# attinier84-motherboard-mk-4_0.net
KiCad netlist of a schematic drawn in EAGLE
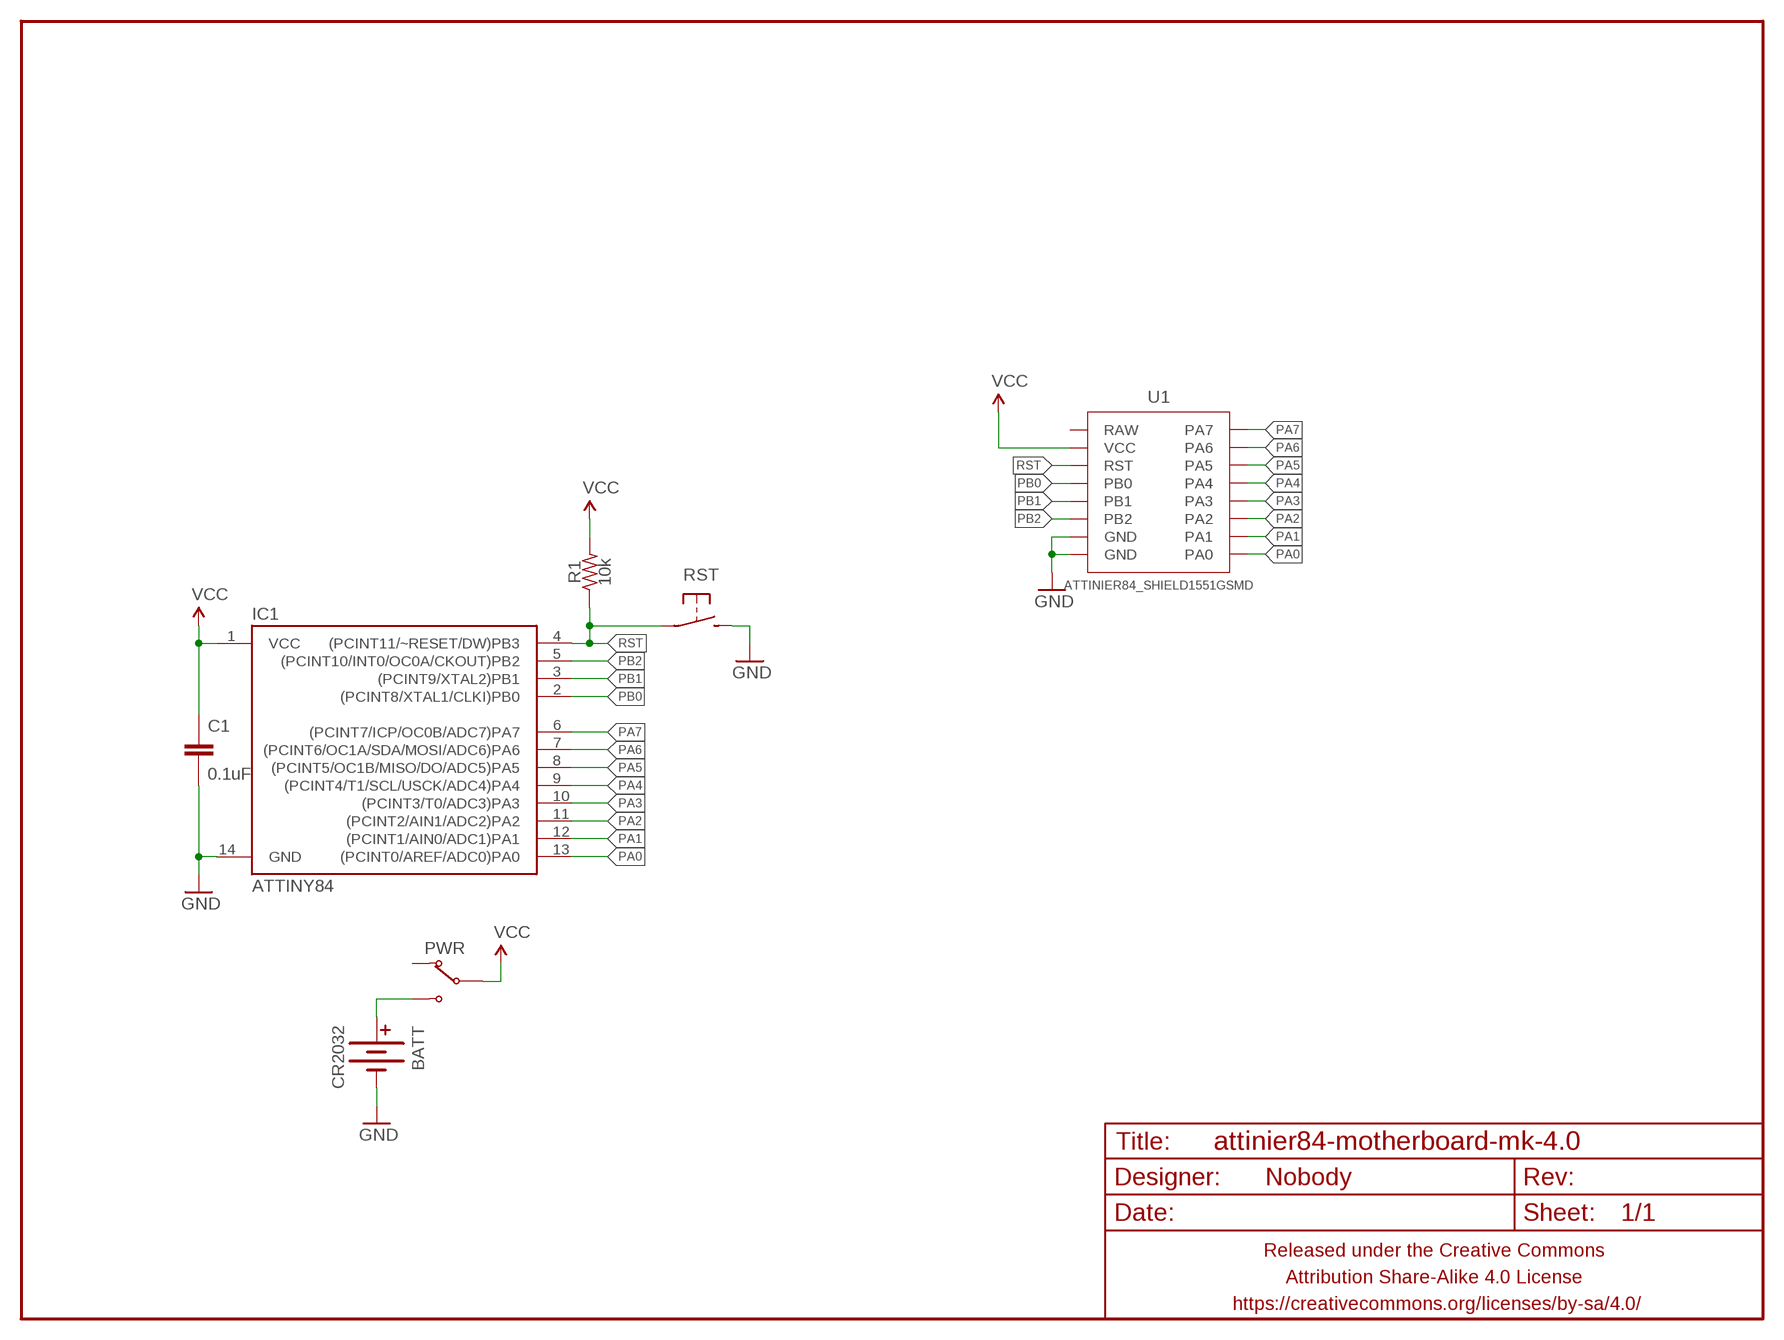
[diagram p0: schematic, sheet 1]

(export (version "E")
  (design (tool "Eeschema 10.0.6"))
  (components
    (comp (ref "BATT")
      (value "CR2032")
      (footprint "eagle-import:BATTCON_20MM_MINE_STAHPIT")
      (libsource (lib "eagle-import") (part "BATTERY20MM_SMD_TIGHT"))
    )
    (comp (ref "C1")
      (value "0.1uF")
      (footprint "eagle-import:C0805")
      (libsource (lib "eagle-import") (part "CAPACITOR-CERAMICC0805"))
    )
    (comp (ref "FRAME1")
      (value "FRAME-LETTERNO_PACKAGE")
      (footprint "eagle-import:DUMMY")
      (fields (field (name "DESIGNER") "Nobody"))
      (libsource (lib "eagle-import") (part "FRAME-LETTERNO_PACKAGE"))
    )
    (comp (ref "IC1")
      (value "ATTINY84")
      (footprint "eagle-import:SO14")
      (libsource (lib "eagle-import") (part "ATTINY84"))
    )
    (comp (ref "PWR")
      (value "SWITCH-SPDTPTH-RA-2.54MM")
      (footprint "eagle-import:SPDT-RA-2.54MM")
      (libsource (lib "eagle-import") (part "SWITCH-SPDTPTH-RA-2.54MM"))
    )
    (comp (ref "R1")
      (value "10k")
      (footprint "eagle-import:R0805")
      (libsource (lib "eagle-import") (part "RESISTORR0805"))
    )
    (comp (ref "RST")
      (value "SPST-NO-TACTCK-PTS840-GK")
      (footprint "eagle-import:TACTILE-SMD-CK-PTS840-GK")
      (libsource (lib "eagle-import") (part "SPST-NO-TACTCK-PTS840-GK"))
    )
    (comp (ref "U1")
      (value "ATTINIER84_SHIELD1551GSMD")
      (footprint "eagle-import:ATTINIER84_SHIELD2_SMD")
      (libsource (lib "eagle-import") (part "ATTINIER84_SHIELD1551GSMD"))
    )
  )
  (nets
    (net (code "1") (name "GND") (class "Default")
      (node (ref "BATT") (pin "BOTTOM") (pinfunction "-_BOTTOM") (pintype "power_in"))
      (node (ref "C1") (pin "2") (pinfunction "2_2") (pintype "passive"))
      (node (ref "IC1") (pin "14") (pinfunction "GND_14") (pintype "bidirectional"))
      (node (ref "RST") (pin "3") (pinfunction "2_3") (pintype "passive"))
      (node (ref "RST") (pin "4") (pinfunction "2_4") (pintype "passive"))
      (node (ref "U1") (pin "GND@1") (pinfunction "GND_GND@1") (pintype "bidirectional"))
      (node (ref "U1") (pin "GND@2") (pinfunction "GND_GND@2") (pintype "bidirectional"))
    )
    (net (code "2") (name "Net-(PWR-NO)") (class "Default")
      (node (ref "BATT") (pin "TOP@1") (pinfunction "+_TOP@1") (pintype "power_in"))
      (node (ref "BATT") (pin "TOP@2") (pinfunction "+_TOP@2") (pintype "power_in"))
      (node (ref "PWR") (pin "3") (pinfunction "NO_3") (pintype "passive"))
    )
    (net (code "3") (name "PA0") (class "Default")
      (node (ref "IC1") (pin "13") (pinfunction "(PCINT0/AREF/ADC0)PA0_13") (pintype "bidirectional"))
      (node (ref "U1") (pin "PA0") (pinfunction "PA0_PA0") (pintype "bidirectional"))
    )
    (net (code "4") (name "PA1") (class "Default")
      (node (ref "IC1") (pin "12") (pinfunction "(PCINT1/AIN0/ADC1)PA1_12") (pintype "bidirectional"))
      (node (ref "U1") (pin "PA1") (pinfunction "PA1_PA1") (pintype "bidirectional"))
    )
    (net (code "5") (name "PA2") (class "Default")
      (node (ref "IC1") (pin "11") (pinfunction "(PCINT2/AIN1/ADC2)PA2_11") (pintype "bidirectional"))
      (node (ref "U1") (pin "PA2") (pinfunction "PA2_PA2") (pintype "bidirectional"))
    )
    (net (code "6") (name "PA3") (class "Default")
      (node (ref "IC1") (pin "10") (pinfunction "(PCINT3/T0/ADC3)PA3_10") (pintype "bidirectional"))
      (node (ref "U1") (pin "PA3") (pinfunction "PA3_PA3") (pintype "bidirectional"))
    )
    (net (code "7") (name "PA4") (class "Default")
      (node (ref "IC1") (pin "9") (pinfunction "(PCINT4/T1/SCL/USCK/ADC4)PA4_9") (pintype "bidirectional"))
      (node (ref "U1") (pin "PA4") (pinfunction "PA4_PA4") (pintype "bidirectional"))
    )
    (net (code "8") (name "PA5") (class "Default")
      (node (ref "IC1") (pin "8") (pinfunction "(PCINT5/OC1B/MISO/DO/ADC5)PA5_8") (pintype "bidirectional"))
      (node (ref "U1") (pin "PA5") (pinfunction "PA5_PA5") (pintype "bidirectional"))
    )
    (net (code "9") (name "PA6") (class "Default")
      (node (ref "IC1") (pin "7") (pinfunction "(PCINT6/OC1A/SDA/MOSI/ADC6)PA6_7") (pintype "bidirectional"))
      (node (ref "U1") (pin "PA6") (pinfunction "PA6_PA6") (pintype "bidirectional"))
    )
    (net (code "10") (name "PA7") (class "Default")
      (node (ref "IC1") (pin "6") (pinfunction "(PCINT7/ICP/OC0B/ADC7)PA7_6") (pintype "bidirectional"))
      (node (ref "U1") (pin "PA7") (pinfunction "PA7_PA7") (pintype "bidirectional"))
    )
    (net (code "11") (name "PB0") (class "Default")
      (node (ref "IC1") (pin "2") (pinfunction "(PCINT8/XTAL1/CLKI)PB0_2") (pintype "bidirectional"))
      (node (ref "U1") (pin "PB0") (pinfunction "PB0_PB0") (pintype "bidirectional"))
    )
    (net (code "12") (name "PB1") (class "Default")
      (node (ref "IC1") (pin "3") (pinfunction "(PCINT9/XTAL2)PB1_3") (pintype "bidirectional"))
      (node (ref "U1") (pin "PB1") (pinfunction "PB1_PB1") (pintype "bidirectional"))
    )
    (net (code "13") (name "PB2") (class "Default")
      (node (ref "IC1") (pin "5") (pinfunction "(PCINT10/INT0/OC0A/CKOUT)PB2_5") (pintype "bidirectional"))
      (node (ref "U1") (pin "PB2") (pinfunction "PB2_PB2") (pintype "bidirectional"))
    )
    (net (code "14") (name "RST") (class "Default")
      (node (ref "IC1") (pin "4") (pinfunction "(PCINT11/~{RESET/DW})PB3_4") (pintype "bidirectional"))
      (node (ref "R1") (pin "1") (pinfunction "1_1") (pintype "passive"))
      (node (ref "RST") (pin "1") (pinfunction "1_1") (pintype "passive"))
      (node (ref "RST") (pin "2") (pinfunction "1_2") (pintype "passive"))
      (node (ref "U1") (pin "RST") (pinfunction "RST_RST") (pintype "bidirectional"))
    )
    (net (code "15") (name "VCC") (class "Default")
      (node (ref "C1") (pin "1") (pinfunction "1_1") (pintype "passive"))
      (node (ref "IC1") (pin "1") (pinfunction "VCC_1") (pintype "bidirectional"))
      (node (ref "PWR") (pin "2") (pinfunction "COM_2") (pintype "passive"))
      (node (ref "R1") (pin "2") (pinfunction "2_2") (pintype "passive"))
      (node (ref "U1") (pin "VCC") (pinfunction "VCC_VCC") (pintype "bidirectional"))
    )
    (net (code "16") (name "unconnected-(PWR-NC-Pad1)") (class "Default")
      (node (ref "PWR") (pin "1") (pinfunction "NC_1") (pintype "passive"))
    )
    (net (code "17") (name "unconnected-(U1-PadRAW)") (class "Default")
      (node (ref "U1") (pin "RAW") (pinfunction "RAW_RAW") (pintype "bidirectional"))
    )
  )
)
